# driver_1.net
KiCad netlist of a schematic drawn in EAGLE
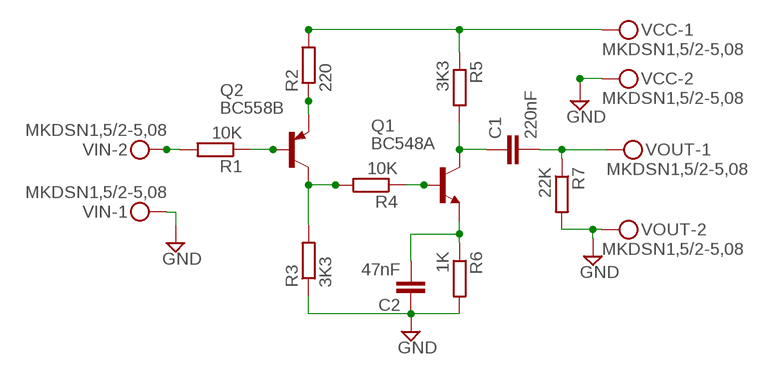
[diagram p0: schematic, sheet 1]

(export (version "E")
  (design (tool "Eeschema 10.0.6"))
  (components
    (comp (ref "C1")
      (value "220nF")
      (footprint "eagle-import:C025-025X050")
      (libsource (lib "eagle-import") (part "C-EU025-025X050"))
    )
    (comp (ref "C2")
      (value "47nF")
      (footprint "eagle-import:C025-025X050")
      (libsource (lib "eagle-import") (part "C-EU025-025X050"))
    )
    (comp (ref "Q1")
      (value "BC548A")
      (footprint "eagle-import:TO92-EBC")
      (libsource (lib "eagle-import") (part "BC548A"))
    )
    (comp (ref "Q2")
      (value "BC558B")
      (footprint "eagle-import:TO92-EBC")
      (libsource (lib "eagle-import") (part "BC558B"))
    )
    (comp (ref "R1")
      (value "10K")
      (footprint "eagle-import:0207_7")
      (libsource (lib "eagle-import") (part "R-EU_0207/7"))
    )
    (comp (ref "R2")
      (value "220")
      (footprint "eagle-import:0207_7")
      (libsource (lib "eagle-import") (part "R-EU_0207/7"))
    )
    (comp (ref "R3")
      (value "3K3")
      (footprint "eagle-import:0207_7")
      (libsource (lib "eagle-import") (part "R-EU_0207/7"))
    )
    (comp (ref "R4")
      (value "10K")
      (footprint "eagle-import:0207_7")
      (libsource (lib "eagle-import") (part "R-EU_0207/7"))
    )
    (comp (ref "R5")
      (value "3K3")
      (footprint "eagle-import:0207_7")
      (libsource (lib "eagle-import") (part "R-EU_0207/7"))
    )
    (comp (ref "R6")
      (value "1K")
      (footprint "eagle-import:0207_7")
      (libsource (lib "eagle-import") (part "R-EU_0207/7"))
    )
    (comp (ref "R7")
      (value "22K")
      (footprint "eagle-import:0207_7")
      (libsource (lib "eagle-import") (part "R-EU_0207/7"))
    )
    (comp (ref "VCC")
      (value "MKDSN1,5/2-5,08")
      (footprint "eagle-import:MKDSN1,5_2-5,08")
      (libsource (lib "eagle-import") (part "MKDSN1,5/2-5,08"))
    )
    (comp (ref "VIN")
      (value "MKDSN1,5/2-5,08")
      (footprint "eagle-import:MKDSN1,5_2-5,08")
      (libsource (lib "eagle-import") (part "MKDSN1,5/2-5,08"))
    )
    (comp (ref "VOUT")
      (value "MKDSN1,5/2-5,08")
      (footprint "eagle-import:MKDSN1,5_2-5,08")
      (libsource (lib "eagle-import") (part "MKDSN1,5/2-5,08"))
    )
  )
  (nets
    (net (code "1") (name "GND") (class "Default")
      (node (ref "C2") (pin "1") (pinfunction "1_1") (pintype "passive"))
      (node (ref "R3") (pin "1") (pinfunction "1_1") (pintype "passive"))
      (node (ref "R6") (pin "2") (pinfunction "2_2") (pintype "passive"))
      (node (ref "R7") (pin "2") (pinfunction "2_2") (pintype "passive"))
      (node (ref "VCC") (pin "2") (pinfunction "KL_2") (pintype "passive"))
      (node (ref "VIN") (pin "1") (pinfunction "KL_1") (pintype "passive"))
      (node (ref "VOUT") (pin "2") (pinfunction "KL_2") (pintype "passive"))
    )
    (net (code "2") (name "Net-(C1-Pad1)") (class "Default")
      (node (ref "C1") (pin "1") (pinfunction "1_1") (pintype "passive"))
      (node (ref "Q1") (pin "C") (pinfunction "C_C") (pintype "passive"))
      (node (ref "R5") (pin "2") (pinfunction "2_2") (pintype "passive"))
    )
    (net (code "3") (name "Net-(C2-Pad2)") (class "Default")
      (node (ref "C2") (pin "2") (pinfunction "2_2") (pintype "passive"))
      (node (ref "Q1") (pin "E") (pinfunction "E_E") (pintype "passive"))
      (node (ref "R6") (pin "1") (pinfunction "1_1") (pintype "passive"))
    )
    (net (code "4") (name "Net-(Q1-PadB)") (class "Default")
      (node (ref "Q1") (pin "B") (pinfunction "B_B") (pintype "passive"))
      (node (ref "R4") (pin "1") (pinfunction "1_1") (pintype "passive"))
    )
    (net (code "5") (name "Net-(Q2-PadB)") (class "Default")
      (node (ref "Q2") (pin "B") (pinfunction "B_B") (pintype "passive"))
      (node (ref "R1") (pin "1") (pinfunction "1_1") (pintype "passive"))
    )
    (net (code "6") (name "Net-(Q2-PadC)") (class "Default")
      (node (ref "Q2") (pin "C") (pinfunction "C_C") (pintype "passive"))
      (node (ref "R3") (pin "2") (pinfunction "2_2") (pintype "passive"))
      (node (ref "R4") (pin "2") (pinfunction "2_2") (pintype "passive"))
    )
    (net (code "7") (name "Net-(Q2-PadE)") (class "Default")
      (node (ref "Q2") (pin "E") (pinfunction "E_E") (pintype "passive"))
      (node (ref "R2") (pin "1") (pinfunction "1_1") (pintype "passive"))
    )
    (net (code "8") (name "Net-(VCCA-KL)") (class "Default")
      (node (ref "R2") (pin "2") (pinfunction "2_2") (pintype "passive"))
      (node (ref "R5") (pin "1") (pinfunction "1_1") (pintype "passive"))
      (node (ref "VCC") (pin "1") (pinfunction "KL_1") (pintype "passive"))
    )
    (net (code "9") (name "Net-(VINB-KL)") (class "Default")
      (node (ref "R1") (pin "2") (pinfunction "2_2") (pintype "passive"))
      (node (ref "VIN") (pin "2") (pinfunction "KL_2") (pintype "passive"))
    )
    (net (code "10") (name "Net-(VOUTA-KL)") (class "Default")
      (node (ref "C1") (pin "2") (pinfunction "2_2") (pintype "passive"))
      (node (ref "R7") (pin "1") (pinfunction "1_1") (pintype "passive"))
      (node (ref "VOUT") (pin "1") (pinfunction "KL_1") (pintype "passive"))
    )
  )
)
